# NucleoSheet.net
KiCad netlist of a schematic drawn in Altium Designer
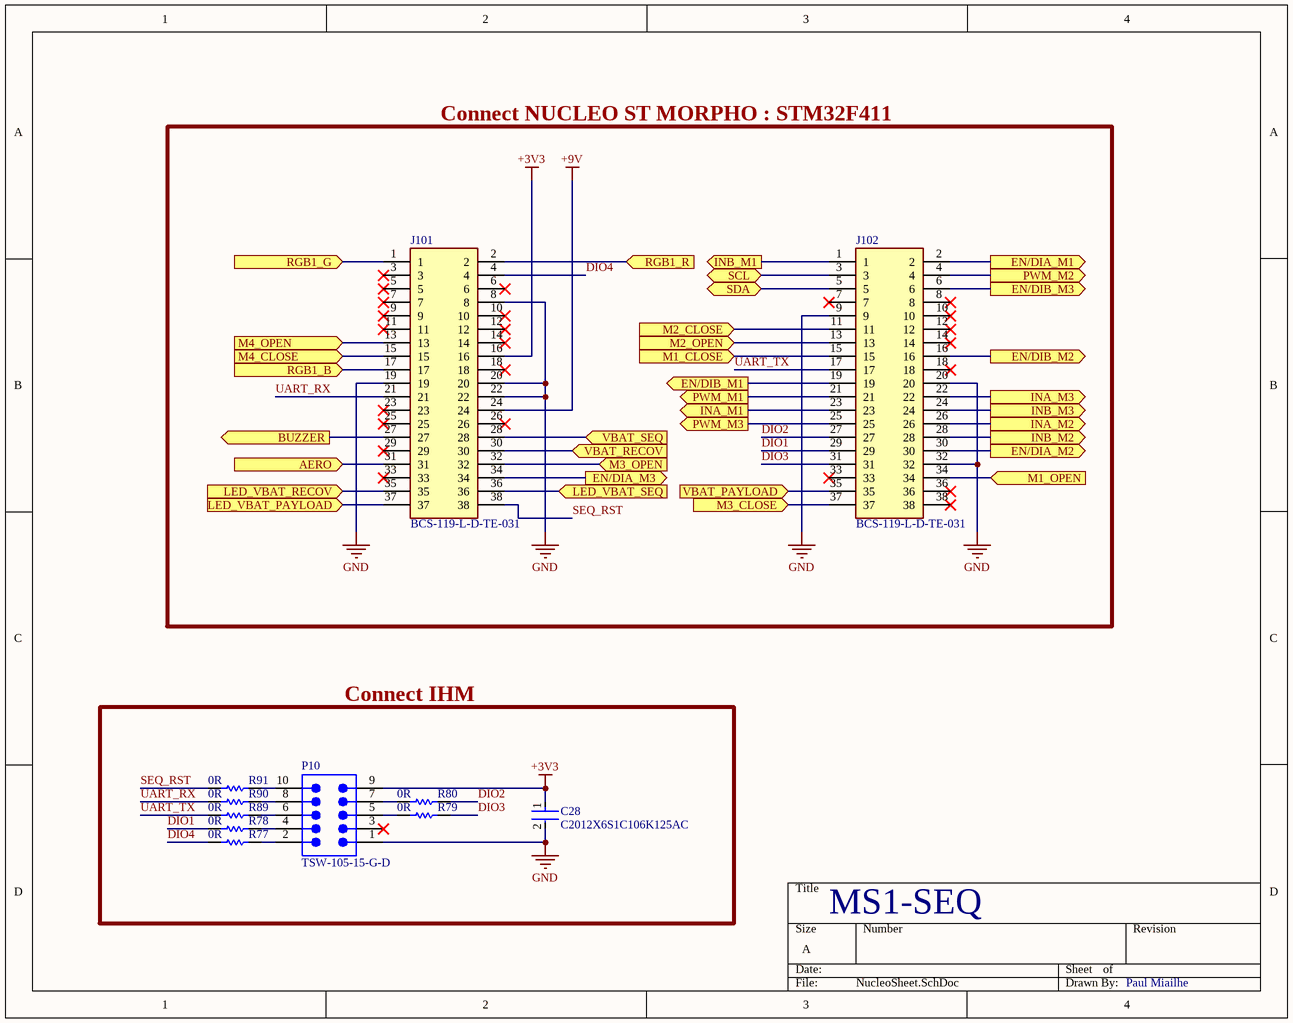
[diagram p0: NucleoSheet.SchDoc]

(export (version "E")
  (design (tool "Eeschema 10.0.6"))
  (components
    (comp (ref "C28")
      (value "C2012X6S1C106K125AC")
      (footprint "FP-C2012-125-0_2-MFG")
      (description "Multilayer Ceramic Capacitors 10μF ±10% 16V X6S SMD 0805")
      (fields (field (name "TOLERANCE") "10%"))
      (libsource (lib "Altium Content Vault") (part "b4654b650e69147ec39a6b967a45e02"))
    )
    (comp (ref "J101")
      (value "BCS-119-L-D-TE-031")
      (footprint "SamacSys:RHDR38W51P254_2X19_4826X508X737P")
      (description "Connector")
      (libsource (lib "*") (part "BCS-119-L-D-TE-031"))
    )
    (comp (ref "J102")
      (value "BCS-119-L-D-TE-031")
      (footprint "SamacSys:RHDR38W51P254_2X19_4826X508X737P")
      (description "Connector")
      (libsource (lib "*") (part "BCS-119-L-D-TE-031"))
    )
    (comp (ref "P10")
      (value "TSW-105-15-G-D")
      (footprint "SMTC-TSW-105-15-X-D")
      (description "0.025\" SQ Post Header, Through-hole, Vertical, -55 to 125 degC, 2.54 mm Pitch, 10-Pin, Male, RoHS")
      (fields (field (name "MANUFACTURER") "Samtec"))
      (libsource (lib "Altium Content Vault") (part "SMTC-TSW-105-X-X-D-X"))
    )
    (comp (ref "R77")
      (value "CRCW06030000Z0EA")
      (footprint "RESC1609X50X30NL8T20")
      (description "Chip Resistor, 0 Ohm, Jumper, 100 mW, -55 to 155 degC, 0603 (1608 Metric), RoHS, Tape and Reel")
      (fields (field (name "MANUFACTURER") "Vishay Semiconductor") (field (name "RESISTOR") "0R"))
      (libsource (lib "Altium Content Vault") (part "RES-2"))
    )
    (comp (ref "R78")
      (value "CRCW06030000Z0EA")
      (footprint "RESC1609X50X30NL8T20")
      (description "Chip Resistor, 0 Ohm, Jumper, 100 mW, -55 to 155 degC, 0603 (1608 Metric), RoHS, Tape and Reel")
      (fields (field (name "MANUFACTURER") "Vishay Semiconductor") (field (name "RESISTOR") "0R"))
      (libsource (lib "Altium Content Vault") (part "RES-2"))
    )
    (comp (ref "R79")
      (value "CRCW06030000Z0EA")
      (footprint "RESC1609X50X30NL8T20")
      (description "Chip Resistor, 0 Ohm, Jumper, 100 mW, -55 to 155 degC, 0603 (1608 Metric), RoHS, Tape and Reel")
      (fields (field (name "MANUFACTURER") "Vishay Semiconductor") (field (name "RESISTOR") "0R"))
      (libsource (lib "Altium Content Vault") (part "RES-2"))
    )
    (comp (ref "R80")
      (value "CRCW06030000Z0EA")
      (footprint "RESC1609X50X30NL8T20")
      (description "Chip Resistor, 0 Ohm, Jumper, 100 mW, -55 to 155 degC, 0603 (1608 Metric), RoHS, Tape and Reel")
      (fields (field (name "MANUFACTURER") "Vishay Semiconductor") (field (name "RESISTOR") "0R"))
      (libsource (lib "Altium Content Vault") (part "RES-2"))
    )
    (comp (ref "R89")
      (value "CRCW06030000Z0EA")
      (footprint "RESC1609X50X30NL8T20")
      (description "Chip Resistor, 0 Ohm, Jumper, 100 mW, -55 to 155 degC, 0603 (1608 Metric), RoHS, Tape and Reel")
      (fields (field (name "MANUFACTURER") "Vishay Semiconductor") (field (name "RESISTOR") "0R"))
      (libsource (lib "Altium Content Vault") (part "RES-2"))
    )
    (comp (ref "R90")
      (value "CRCW06030000Z0EA")
      (footprint "RESC1609X50X30NL8T20")
      (description "Chip Resistor, 0 Ohm, Jumper, 100 mW, -55 to 155 degC, 0603 (1608 Metric), RoHS, Tape and Reel")
      (fields (field (name "MANUFACTURER") "Vishay Semiconductor") (field (name "RESISTOR") "0R"))
      (libsource (lib "Altium Content Vault") (part "RES-2"))
    )
    (comp (ref "R91")
      (value "CRCW06030000Z0EA")
      (footprint "RESC1609X50X30NL8T20")
      (description "Chip Resistor, 0 Ohm, Jumper, 100 mW, -55 to 155 degC, 0603 (1608 Metric), RoHS, Tape and Reel")
      (fields (field (name "MANUFACTURER") "Vishay Semiconductor") (field (name "RESISTOR") "0R"))
      (libsource (lib "Altium Content Vault") (part "RES-2"))
    )
  )
  (nets
    (net (code "1") (name "+3V3") (class "Default")
      (node (ref "C28") (pin "1") (pinfunction "1_1") (pintype "passive"))
      (node (ref "J101") (pin "16") (pinfunction "16_16") (pintype "passive"))
      (node (ref "P10") (pin "9") (pinfunction "9_9") (pintype "passive"))
    )
    (net (code "2") (name "+9V") (class "Default")
      (node (ref "J101") (pin "24") (pinfunction "24_24") (pintype "passive"))
    )
    (net (code "3") (name "/AERO") (class "Default")
      (node (ref "J101") (pin "31") (pinfunction "31_31") (pintype "passive"))
    )
    (net (code "4") (name "/BUZZER") (class "Default")
      (node (ref "J101") (pin "27") (pinfunction "27_27") (pintype "passive"))
    )
    (net (code "5") (name "/DIO1") (class "Default")
      (node (ref "J102") (pin "29") (pinfunction "29_29") (pintype "passive"))
      (node (ref "R78") (pin "1") (pinfunction "1_1") (pintype "passive"))
    )
    (net (code "6") (name "/DIO2") (class "Default")
      (node (ref "J102") (pin "27") (pinfunction "27_27") (pintype "passive"))
      (node (ref "R80") (pin "2") (pinfunction "2_2") (pintype "passive"))
    )
    (net (code "7") (name "/DIO3") (class "Default")
      (node (ref "J102") (pin "31") (pinfunction "31_31") (pintype "passive"))
      (node (ref "R79") (pin "2") (pinfunction "2_2") (pintype "passive"))
    )
    (net (code "8") (name "/DIO4") (class "Default")
      (node (ref "J101") (pin "4") (pinfunction "4_4") (pintype "passive"))
      (node (ref "R77") (pin "1") (pinfunction "1_1") (pintype "passive"))
    )
    (net (code "9") (name "/EN{slash}DIA_M1") (class "Default")
      (node (ref "J102") (pin "2") (pinfunction "2_2") (pintype "passive"))
    )
    (net (code "10") (name "/EN{slash}DIA_M2") (class "Default")
      (node (ref "J102") (pin "30") (pinfunction "30_30") (pintype "passive"))
    )
    (net (code "11") (name "/EN{slash}DIA_M3") (class "Default")
      (node (ref "J101") (pin "34") (pinfunction "34_34") (pintype "passive"))
    )
    (net (code "12") (name "/EN{slash}DIB_M1") (class "Default")
      (node (ref "J102") (pin "19") (pinfunction "19_19") (pintype "passive"))
    )
    (net (code "13") (name "/EN{slash}DIB_M2") (class "Default")
      (node (ref "J102") (pin "16") (pinfunction "16_16") (pintype "passive"))
    )
    (net (code "14") (name "/EN{slash}DIB_M3") (class "Default")
      (node (ref "J102") (pin "6") (pinfunction "6_6") (pintype "passive"))
    )
    (net (code "15") (name "/INA_M1") (class "Default")
      (node (ref "J102") (pin "23") (pinfunction "23_23") (pintype "passive"))
    )
    (net (code "16") (name "/INA_M2") (class "Default")
      (node (ref "J102") (pin "26") (pinfunction "26_26") (pintype "passive"))
    )
    (net (code "17") (name "/INA_M3") (class "Default")
      (node (ref "J102") (pin "22") (pinfunction "22_22") (pintype "passive"))
    )
    (net (code "18") (name "/INB_M1") (class "Default")
      (node (ref "J102") (pin "1") (pinfunction "1_1") (pintype "passive"))
    )
    (net (code "19") (name "/INB_M2") (class "Default")
      (node (ref "J102") (pin "28") (pinfunction "28_28") (pintype "passive"))
    )
    (net (code "20") (name "/INB_M3") (class "Default")
      (node (ref "J102") (pin "24") (pinfunction "24_24") (pintype "passive"))
    )
    (net (code "21") (name "/LED_VBAT_PAYLOAD") (class "Default")
      (node (ref "J101") (pin "37") (pinfunction "37_37") (pintype "passive"))
    )
    (net (code "22") (name "/LED_VBAT_RECOV") (class "Default")
      (node (ref "J101") (pin "35") (pinfunction "35_35") (pintype "passive"))
    )
    (net (code "23") (name "/LED_VBAT_SEQ") (class "Default")
      (node (ref "J101") (pin "36") (pinfunction "36_36") (pintype "passive"))
    )
    (net (code "24") (name "/M1_CLOSE") (class "Default")
      (node (ref "J102") (pin "15") (pinfunction "15_15") (pintype "passive"))
    )
    (net (code "25") (name "/M1_OPEN") (class "Default")
      (node (ref "J102") (pin "34") (pinfunction "34_34") (pintype "passive"))
    )
    (net (code "26") (name "/M2_CLOSE") (class "Default")
      (node (ref "J102") (pin "11") (pinfunction "11_11") (pintype "passive"))
    )
    (net (code "27") (name "/M2_OPEN") (class "Default")
      (node (ref "J102") (pin "13") (pinfunction "13_13") (pintype "passive"))
    )
    (net (code "28") (name "/M3_CLOSE") (class "Default")
      (node (ref "J102") (pin "37") (pinfunction "37_37") (pintype "passive"))
    )
    (net (code "29") (name "/M3_OPEN") (class "Default")
      (node (ref "J101") (pin "32") (pinfunction "32_32") (pintype "passive"))
    )
    (net (code "30") (name "/M4_CLOSE") (class "Default")
      (node (ref "J101") (pin "15") (pinfunction "15_15") (pintype "passive"))
    )
    (net (code "31") (name "/M4_OPEN") (class "Default")
      (node (ref "J101") (pin "13") (pinfunction "13_13") (pintype "passive"))
    )
    (net (code "32") (name "/PWM_M1") (class "Default")
      (node (ref "J102") (pin "21") (pinfunction "21_21") (pintype "passive"))
    )
    (net (code "33") (name "/PWM_M2") (class "Default")
      (node (ref "J102") (pin "4") (pinfunction "4_4") (pintype "passive"))
    )
    (net (code "34") (name "/PWM_M3") (class "Default")
      (node (ref "J102") (pin "25") (pinfunction "25_25") (pintype "passive"))
    )
    (net (code "35") (name "/RGB1_B") (class "Default")
      (node (ref "J101") (pin "17") (pinfunction "17_17") (pintype "passive"))
    )
    (net (code "36") (name "/RGB1_G") (class "Default")
      (node (ref "J101") (pin "1") (pinfunction "1_1") (pintype "passive"))
    )
    (net (code "37") (name "/RGB1_R") (class "Default")
      (node (ref "J101") (pin "2") (pinfunction "2_2") (pintype "passive"))
    )
    (net (code "38") (name "/SCL") (class "Default")
      (node (ref "J102") (pin "3") (pinfunction "3_3") (pintype "passive"))
    )
    (net (code "39") (name "/SDA") (class "Default")
      (node (ref "J102") (pin "5") (pinfunction "5_5") (pintype "passive"))
    )
    (net (code "40") (name "/SEQ_RST") (class "Default")
      (node (ref "J101") (pin "38") (pinfunction "38_38") (pintype "passive"))
      (node (ref "R91") (pin "1") (pinfunction "1_1") (pintype "passive"))
    )
    (net (code "41") (name "/UART_RX") (class "Default")
      (node (ref "J101") (pin "21") (pinfunction "21_21") (pintype "passive"))
      (node (ref "R90") (pin "1") (pinfunction "1_1") (pintype "passive"))
    )
    (net (code "42") (name "/UART_TX") (class "Default")
      (node (ref "J102") (pin "17") (pinfunction "17_17") (pintype "passive"))
      (node (ref "R89") (pin "1") (pinfunction "1_1") (pintype "passive"))
    )
    (net (code "43") (name "/VBAT_PAYLOAD") (class "Default")
      (node (ref "J102") (pin "35") (pinfunction "35_35") (pintype "passive"))
    )
    (net (code "44") (name "/VBAT_RECOV") (class "Default")
      (node (ref "J101") (pin "30") (pinfunction "30_30") (pintype "passive"))
    )
    (net (code "45") (name "/VBAT_SEQ") (class "Default")
      (node (ref "J101") (pin "28") (pinfunction "28_28") (pintype "passive"))
    )
    (net (code "46") (name "GND") (class "Default")
      (node (ref "C28") (pin "2") (pinfunction "2_2") (pintype "passive"))
      (node (ref "J101") (pin "19") (pinfunction "19_19") (pintype "passive"))
      (node (ref "J101") (pin "20") (pinfunction "20_20") (pintype "passive"))
      (node (ref "J101") (pin "22") (pinfunction "22_22") (pintype "passive"))
      (node (ref "J101") (pin "8") (pinfunction "8_8") (pintype "passive"))
      (node (ref "J102") (pin "20") (pinfunction "20_20") (pintype "passive"))
      (node (ref "J102") (pin "32") (pinfunction "32_32") (pintype "passive"))
      (node (ref "J102") (pin "9") (pinfunction "9_9") (pintype "passive"))
      (node (ref "P10") (pin "1") (pinfunction "1_1") (pintype "passive"))
    )
    (net (code "47") (name "Net-(P10-Pad2)") (class "Default")
      (node (ref "P10") (pin "2") (pinfunction "2_2") (pintype "passive"))
      (node (ref "R77") (pin "2") (pinfunction "2_2") (pintype "passive"))
    )
    (net (code "48") (name "Net-(P10-Pad4)") (class "Default")
      (node (ref "P10") (pin "4") (pinfunction "4_4") (pintype "passive"))
      (node (ref "R78") (pin "2") (pinfunction "2_2") (pintype "passive"))
    )
    (net (code "49") (name "Net-(P10-Pad5)") (class "Default")
      (node (ref "P10") (pin "5") (pinfunction "5_5") (pintype "passive"))
      (node (ref "R79") (pin "1") (pinfunction "1_1") (pintype "passive"))
    )
    (net (code "50") (name "Net-(P10-Pad6)") (class "Default")
      (node (ref "P10") (pin "6") (pinfunction "6_6") (pintype "passive"))
      (node (ref "R89") (pin "2") (pinfunction "2_2") (pintype "passive"))
    )
    (net (code "51") (name "Net-(P10-Pad7)") (class "Default")
      (node (ref "P10") (pin "7") (pinfunction "7_7") (pintype "passive"))
      (node (ref "R80") (pin "1") (pinfunction "1_1") (pintype "passive"))
    )
    (net (code "52") (name "Net-(P10-Pad8)") (class "Default")
      (node (ref "P10") (pin "8") (pinfunction "8_8") (pintype "passive"))
      (node (ref "R90") (pin "2") (pinfunction "2_2") (pintype "passive"))
    )
    (net (code "53") (name "Net-(P10-Pad10)") (class "Default")
      (node (ref "P10") (pin "10") (pinfunction "10_10") (pintype "passive"))
      (node (ref "R91") (pin "2") (pinfunction "2_2") (pintype "passive"))
    )
    (net (code "54") (name "unconnected-(J101-Pad3)") (class "Default")
      (node (ref "J101") (pin "3") (pinfunction "3_3") (pintype "passive+no_connect"))
    )
    (net (code "55") (name "unconnected-(J101-Pad5)") (class "Default")
      (node (ref "J101") (pin "5") (pinfunction "5_5") (pintype "passive+no_connect"))
    )
    (net (code "56") (name "unconnected-(J101-Pad6)") (class "Default")
      (node (ref "J101") (pin "6") (pinfunction "6_6") (pintype "passive+no_connect"))
    )
    (net (code "57") (name "unconnected-(J101-Pad7)") (class "Default")
      (node (ref "J101") (pin "7") (pinfunction "7_7") (pintype "passive+no_connect"))
    )
    (net (code "58") (name "unconnected-(J101-Pad9)") (class "Default")
      (node (ref "J101") (pin "9") (pinfunction "9_9") (pintype "passive+no_connect"))
    )
    (net (code "59") (name "unconnected-(J101-Pad10)") (class "Default")
      (node (ref "J101") (pin "10") (pinfunction "10_10") (pintype "passive+no_connect"))
    )
    (net (code "60") (name "unconnected-(J101-Pad11)") (class "Default")
      (node (ref "J101") (pin "11") (pinfunction "11_11") (pintype "passive+no_connect"))
    )
    (net (code "61") (name "unconnected-(J101-Pad12)") (class "Default")
      (node (ref "J101") (pin "12") (pinfunction "12_12") (pintype "passive+no_connect"))
    )
    (net (code "62") (name "unconnected-(J101-Pad14)") (class "Default")
      (node (ref "J101") (pin "14") (pinfunction "14_14") (pintype "passive+no_connect"))
    )
    (net (code "63") (name "unconnected-(J101-Pad18)") (class "Default")
      (node (ref "J101") (pin "18") (pinfunction "18_18") (pintype "passive+no_connect"))
    )
    (net (code "64") (name "unconnected-(J101-Pad23)") (class "Default")
      (node (ref "J101") (pin "23") (pinfunction "23_23") (pintype "passive+no_connect"))
    )
    (net (code "65") (name "unconnected-(J101-Pad25)") (class "Default")
      (node (ref "J101") (pin "25") (pinfunction "25_25") (pintype "passive+no_connect"))
    )
    (net (code "66") (name "unconnected-(J101-Pad26)") (class "Default")
      (node (ref "J101") (pin "26") (pinfunction "26_26") (pintype "passive+no_connect"))
    )
    (net (code "67") (name "unconnected-(J101-Pad29)") (class "Default")
      (node (ref "J101") (pin "29") (pinfunction "29_29") (pintype "passive+no_connect"))
    )
    (net (code "68") (name "unconnected-(J101-Pad33)") (class "Default")
      (node (ref "J101") (pin "33") (pinfunction "33_33") (pintype "passive+no_connect"))
    )
    (net (code "69") (name "unconnected-(J102-Pad7)") (class "Default")
      (node (ref "J102") (pin "7") (pinfunction "7_7") (pintype "passive+no_connect"))
    )
    (net (code "70") (name "unconnected-(J102-Pad8)") (class "Default")
      (node (ref "J102") (pin "8") (pinfunction "8_8") (pintype "passive+no_connect"))
    )
    (net (code "71") (name "unconnected-(J102-Pad10)") (class "Default")
      (node (ref "J102") (pin "10") (pinfunction "10_10") (pintype "passive+no_connect"))
    )
    (net (code "72") (name "unconnected-(J102-Pad12)") (class "Default")
      (node (ref "J102") (pin "12") (pinfunction "12_12") (pintype "passive+no_connect"))
    )
    (net (code "73") (name "unconnected-(J102-Pad14)") (class "Default")
      (node (ref "J102") (pin "14") (pinfunction "14_14") (pintype "passive+no_connect"))
    )
    (net (code "74") (name "unconnected-(J102-Pad18)") (class "Default")
      (node (ref "J102") (pin "18") (pinfunction "18_18") (pintype "passive+no_connect"))
    )
    (net (code "75") (name "unconnected-(J102-Pad33)") (class "Default")
      (node (ref "J102") (pin "33") (pinfunction "33_33") (pintype "passive+no_connect"))
    )
    (net (code "76") (name "unconnected-(J102-Pad36)") (class "Default")
      (node (ref "J102") (pin "36") (pinfunction "36_36") (pintype "passive+no_connect"))
    )
    (net (code "77") (name "unconnected-(J102-Pad38)") (class "Default")
      (node (ref "J102") (pin "38") (pinfunction "38_38") (pintype "passive+no_connect"))
    )
    (net (code "78") (name "unconnected-(P10-Pad3)") (class "Default")
      (node (ref "P10") (pin "3") (pinfunction "3_3") (pintype "passive+no_connect"))
    )
  )
)
